# ATtiny85_and_DRV8830_Combo_--_v01.net
KiCad netlist of a schematic drawn in EAGLE
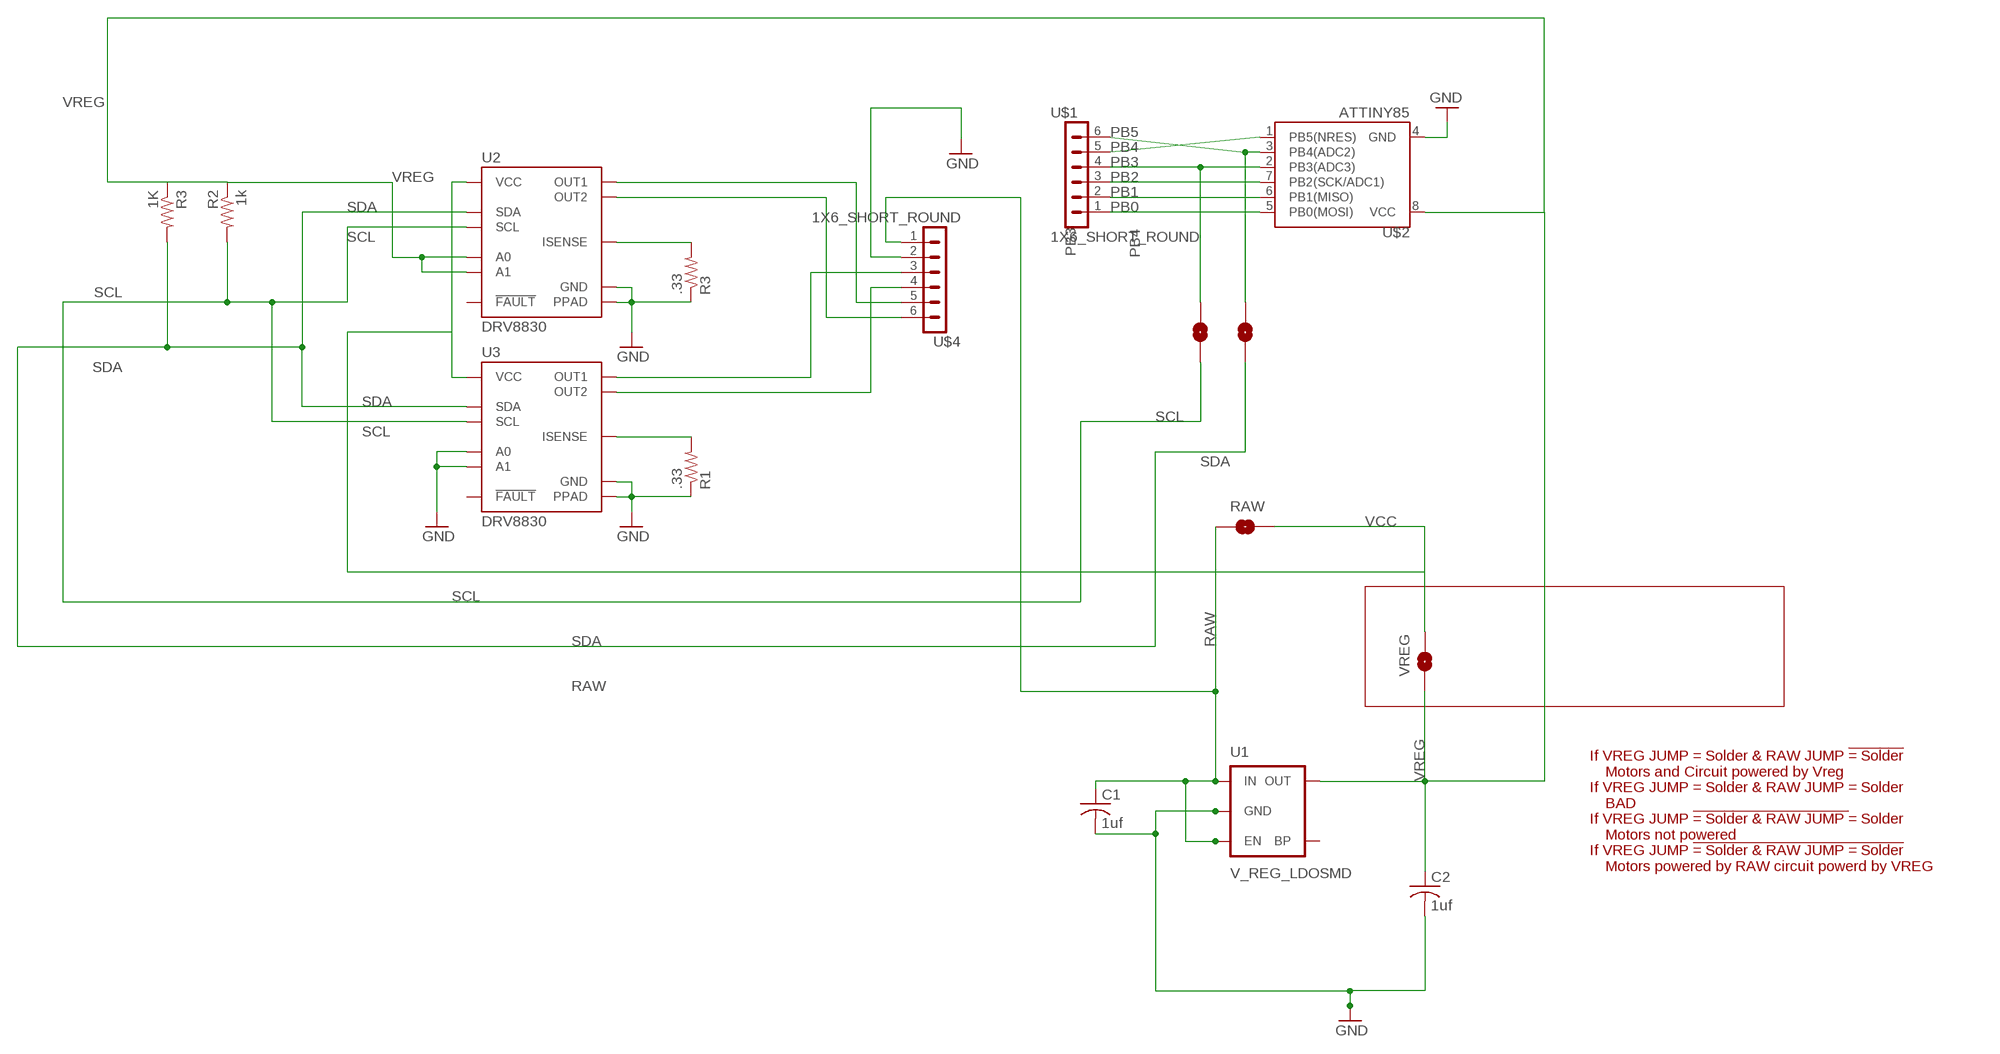
[diagram p0: schematic, sheet 1]

(export (version "E")
  (design (tool "Eeschema 10.0.6"))
  (components
    (comp (ref "1K")
      (value "R3")
      (footprint "eagle-import:R0402")
      (libsource (lib "eagle-import") (part "R-US_R0402"))
    )
    (comp (ref "C1")
      (value "1uf")
      (footprint "eagle-import:C0402")
      (libsource (lib "eagle-import") (part "C-USC0402"))
    )
    (comp (ref "C2")
      (value "1uf")
      (footprint "eagle-import:C0402")
      (libsource (lib "eagle-import") (part "C-USC0402"))
    )
    (comp (ref "R1")
      (value ".33")
      (footprint "eagle-import:R0402")
      (libsource (lib "eagle-import") (part "R-US_R0402"))
    )
    (comp (ref "R2")
      (value "1k")
      (footprint "eagle-import:R0402")
      (libsource (lib "eagle-import") (part "R-US_R0402"))
    )
    (comp (ref "R3")
      (value ".33")
      (footprint "eagle-import:R0402")
      (libsource (lib "eagle-import") (part "R-US_R0402"))
    )
    (comp (ref "RAW")
      (value "SOLDERJUMPERNO")
      (footprint "eagle-import:SJ_2S-NO")
      (libsource (lib "eagle-import") (part "SOLDERJUMPERNO"))
    )
    (comp (ref "SJ6")
      (value "SOLDERJUMPERNO")
      (footprint "eagle-import:SJ_2S-NO")
      (libsource (lib "eagle-import") (part "SOLDERJUMPERNO"))
    )
    (comp (ref "SJ7")
      (value "SOLDERJUMPERNO")
      (footprint "eagle-import:SJ_2S-NO")
      (libsource (lib "eagle-import") (part "SOLDERJUMPERNO"))
    )
    (comp (ref "U$1")
      (value "1X6_SHORT_ROUND")
      (footprint "eagle-import:1X6_SHORT_ROUND")
      (libsource (lib "eagle-import") (part "1X6_SHORT_ROUND"))
    )
    (comp (ref "U$2")
      (value "ATTINY85")
      (footprint "eagle-import:SO08-EIAJ")
      (libsource (lib "eagle-import") (part "ATTINY45"))
    )
    (comp (ref "U$4")
      (value "1X6_SHORT_ROUND")
      (footprint "eagle-import:1X6_SHORT_ROUND")
      (libsource (lib "eagle-import") (part "1X6_SHORT_ROUND"))
    )
    (comp (ref "U1")
      (value "V_REG_LDOSMD")
      (footprint "eagle-import:SOT23-5")
      (libsource (lib "eagle-import") (part "V_REG_LDOSMD"))
    )
    (comp (ref "U2")
      (value "DRV8830")
      (footprint "eagle-import:MSOP-10-GNDPAD")
      (libsource (lib "eagle-import") (part "DRV8830"))
    )
    (comp (ref "U3")
      (value "DRV8830")
      (footprint "eagle-import:MSOP-10-GNDPAD")
      (libsource (lib "eagle-import") (part "DRV8830"))
    )
    (comp (ref "VREG")
      (value "SOLDERJUMPERNO")
      (footprint "eagle-import:SJ_2S-NO")
      (libsource (lib "eagle-import") (part "SOLDERJUMPERNO"))
    )
  )
  (nets
    (net (code "1") (name "/PB0") (class "Default")
      (node (ref "U$1") (pin "1") (pinfunction "1_1") (pintype "passive"))
      (node (ref "U$2") (pin "5") (pinfunction "PB0(MOSI)_5") (pintype "bidirectional"))
    )
    (net (code "2") (name "/PB1") (class "Default")
      (node (ref "U$1") (pin "2") (pinfunction "2_2") (pintype "passive"))
      (node (ref "U$2") (pin "6") (pinfunction "PB1(MISO)_6") (pintype "bidirectional"))
    )
    (net (code "3") (name "/PB2") (class "Default")
      (node (ref "U$1") (pin "3") (pinfunction "3_3") (pintype "passive"))
      (node (ref "U$2") (pin "7") (pinfunction "PB2(SCK/ADC1)_7") (pintype "bidirectional"))
    )
    (net (code "4") (name "/PB3") (class "Default")
      (node (ref "SJ7") (pin "2") (pinfunction "2_2") (pintype "passive"))
      (node (ref "U$1") (pin "4") (pinfunction "4_4") (pintype "passive"))
      (node (ref "U$2") (pin "2") (pinfunction "PB3(ADC3)_2") (pintype "bidirectional"))
    )
    (net (code "5") (name "/PB4") (class "Default")
      (node (ref "SJ6") (pin "2") (pinfunction "2_2") (pintype "passive"))
      (node (ref "U$1") (pin "6") (pinfunction "6_6") (pintype "passive"))
      (node (ref "U$2") (pin "3") (pinfunction "PB4(ADC2)_3") (pintype "bidirectional"))
    )
    (net (code "6") (name "/PB5") (class "Default")
      (node (ref "U$1") (pin "5") (pinfunction "5_5") (pintype "passive"))
      (node (ref "U$2") (pin "1") (pinfunction "PB5(NRES)_1") (pintype "bidirectional"))
    )
    (net (code "7") (name "/RAW") (class "Default")
      (node (ref "C1") (pin "1") (pinfunction "1_1") (pintype "passive"))
      (node (ref "RAW") (pin "1") (pinfunction "1_1") (pintype "passive"))
      (node (ref "U$4") (pin "1") (pinfunction "1_1") (pintype "passive"))
      (node (ref "U1") (pin "1") (pinfunction "IN_1") (pintype "input"))
      (node (ref "U1") (pin "3") (pinfunction "EN_3") (pintype "input"))
    )
    (net (code "8") (name "/SCL") (class "Default")
      (node (ref "R2") (pin "2") (pinfunction "2_2") (pintype "passive"))
      (node (ref "SJ7") (pin "1") (pinfunction "1_1") (pintype "passive"))
      (node (ref "U2") (pin "10") (pinfunction "SCL_10") (pintype "input"))
      (node (ref "U3") (pin "10") (pinfunction "SCL_10") (pintype "input"))
    )
    (net (code "9") (name "/SDA") (class "Default")
      (node (ref "1K") (pin "2") (pinfunction "2_2") (pintype "passive"))
      (node (ref "SJ6") (pin "1") (pinfunction "1_1") (pintype "passive"))
      (node (ref "U2") (pin "9") (pinfunction "SDA_9") (pintype "bidirectional"))
      (node (ref "U3") (pin "9") (pinfunction "SDA_9") (pintype "bidirectional"))
    )
    (net (code "10") (name "/VCC") (class "Default")
      (node (ref "RAW") (pin "2") (pinfunction "2_2") (pintype "passive"))
      (node (ref "U2") (pin "4") (pinfunction "VCC_4") (pintype "power_in"))
      (node (ref "U3") (pin "4") (pinfunction "VCC_4") (pintype "power_in"))
      (node (ref "VREG") (pin "2") (pinfunction "2_2") (pintype "passive"))
    )
    (net (code "11") (name "/VREG") (class "Default")
      (node (ref "1K") (pin "1") (pinfunction "1_1") (pintype "passive"))
      (node (ref "C2") (pin "1") (pinfunction "1_1") (pintype "passive"))
      (node (ref "R2") (pin "1") (pinfunction "1_1") (pintype "passive"))
      (node (ref "U$2") (pin "8") (pinfunction "VCC_8") (pintype "bidirectional"))
      (node (ref "U1") (pin "5") (pinfunction "OUT_5") (pintype "passive"))
      (node (ref "U2") (pin "7") (pinfunction "A0_7") (pintype "input"))
      (node (ref "U2") (pin "8") (pinfunction "A1_8") (pintype "input"))
      (node (ref "VREG") (pin "1") (pinfunction "1_1") (pintype "passive"))
    )
    (net (code "12") (name "GND") (class "Default")
      (node (ref "C1") (pin "2") (pinfunction "2_2") (pintype "passive"))
      (node (ref "C2") (pin "2") (pinfunction "2_2") (pintype "passive"))
      (node (ref "R1") (pin "1") (pinfunction "1_1") (pintype "passive"))
      (node (ref "R3") (pin "1") (pinfunction "1_1") (pintype "passive"))
      (node (ref "U$2") (pin "4") (pinfunction "GND_4") (pintype "bidirectional"))
      (node (ref "U$4") (pin "2") (pinfunction "2_2") (pintype "passive"))
      (node (ref "U1") (pin "2") (pinfunction "GND_2") (pintype "input"))
      (node (ref "U2") (pin "5") (pinfunction "GND_5") (pintype "power_in"))
      (node (ref "U2") (pin "GND") (pinfunction "PPAD_GND") (pintype "power_in"))
      (node (ref "U3") (pin "5") (pinfunction "GND_5") (pintype "power_in"))
      (node (ref "U3") (pin "7") (pinfunction "A0_7") (pintype "input"))
      (node (ref "U3") (pin "8") (pinfunction "A1_8") (pintype "input"))
      (node (ref "U3") (pin "GND") (pinfunction "PPAD_GND") (pintype "power_in"))
    )
    (net (code "13") (name "Net-(U2-ISENSE)") (class "Default")
      (node (ref "R3") (pin "2") (pinfunction "2_2") (pintype "passive"))
      (node (ref "U2") (pin "2") (pinfunction "ISENSE_2") (pintype "bidirectional"))
    )
    (net (code "14") (name "Net-(U2-OUT1)") (class "Default")
      (node (ref "U$4") (pin "5") (pinfunction "5_5") (pintype "passive"))
      (node (ref "U2") (pin "3") (pinfunction "OUT1_3") (pintype "power_in"))
    )
    (net (code "15") (name "Net-(U2-OUT2)") (class "Default")
      (node (ref "U$4") (pin "6") (pinfunction "6_6") (pintype "passive"))
      (node (ref "U2") (pin "1") (pinfunction "OUT2_1") (pintype "power_in"))
    )
    (net (code "16") (name "Net-(U3-ISENSE)") (class "Default")
      (node (ref "R1") (pin "2") (pinfunction "2_2") (pintype "passive"))
      (node (ref "U3") (pin "2") (pinfunction "ISENSE_2") (pintype "bidirectional"))
    )
    (net (code "17") (name "Net-(U3-OUT1)") (class "Default")
      (node (ref "U$4") (pin "3") (pinfunction "3_3") (pintype "passive"))
      (node (ref "U3") (pin "3") (pinfunction "OUT1_3") (pintype "power_in"))
    )
    (net (code "18") (name "Net-(U3-OUT2)") (class "Default")
      (node (ref "U$4") (pin "4") (pinfunction "4_4") (pintype "passive"))
      (node (ref "U3") (pin "1") (pinfunction "OUT2_1") (pintype "power_in"))
    )
    (net (code "19") (name "unconnected-(U1-BP-Pad4)") (class "Default")
      (node (ref "U1") (pin "4") (pinfunction "BP_4") (pintype "input"))
    )
    (net (code "20") (name "unconnected-(U2-~{FAULT}-Pad6)") (class "Default")
      (node (ref "U2") (pin "6") (pinfunction "~{FAULT}_6") (pintype "output"))
    )
    (net (code "21") (name "unconnected-(U3-~{FAULT}-Pad6)") (class "Default")
      (node (ref "U3") (pin "6") (pinfunction "~{FAULT}_6") (pintype "output"))
    )
  )
)
